# power_supply.net
KiCad netlist of a schematic drawn in Altium Designer
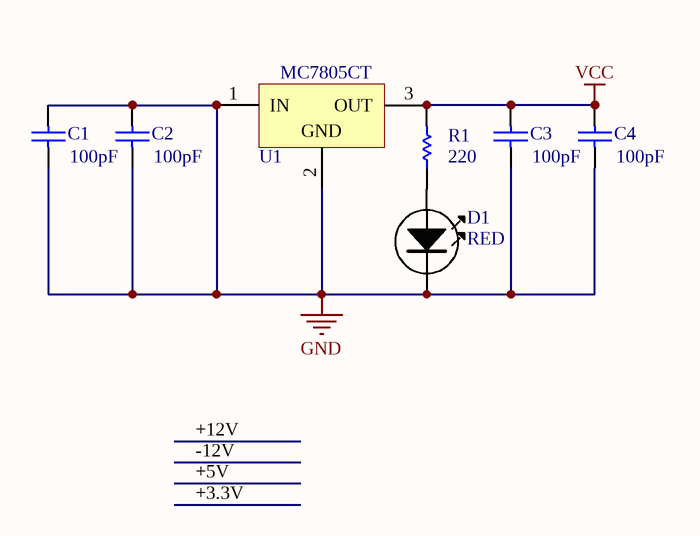
[diagram p0: power_supply.SchDoc]

(export (version "E")
  (design (tool "Eeschema 10.0.6"))
  (components
    (comp (ref "C1")
      (value "100pF")
      (footprint "RAD-0.3")
      (description "Capacitor")
      (fields (field (name "Comment") "Cap") (field (name "PUBLISHER") "Altium Limited"))
      (libsource (lib "Miscellaneous Devices") (part "Cap"))
    )
    (comp (ref "C2")
      (value "100pF")
      (footprint "RAD-0.3")
      (description "Capacitor")
      (fields (field (name "Comment") "Cap") (field (name "PUBLISHER") "Altium Limited"))
      (libsource (lib "Miscellaneous Devices") (part "Cap"))
    )
    (comp (ref "C3")
      (value "100pF")
      (footprint "RAD-0.3")
      (description "Capacitor")
      (fields (field (name "Comment") "Cap") (field (name "PUBLISHER") "Altium Limited"))
      (libsource (lib "Miscellaneous Devices") (part "Cap"))
    )
    (comp (ref "C4")
      (value "100pF")
      (footprint "RAD-0.3")
      (description "Capacitor")
      (fields (field (name "Comment") "Cap") (field (name "PUBLISHER") "Altium Limited"))
      (libsource (lib "Miscellaneous Devices") (part "Cap"))
    )
    (comp (ref "D1")
      (value "RED")
      (footprint "LED-5MM-RED")
      (description "LED-RED-5MM")
      (libsource (lib "vh_altium_library") (part "LED-RED-5MM"))
    )
    (comp (ref "R1")
      (value "220")
      (footprint "AXIAL-0.3")
      (description "Resistor")
      (fields (field (name "PUBLISHER") "Altium Limited"))
      (libsource (lib "Miscellaneous Devices") (part "Res1"))
    )
    (comp (ref "U1")
      (value "MC7805CT")
      (footprint "221A-06")
      (description "Three-Terminal Positive Voltage Regulator")
      (fields (field (name "PUBLISHER") "Altium Limited"))
      (libsource (lib "ON Semi Power Mgt Voltage Regulator") (part "MC7805CT"))
    )
  )
  (nets
    (net (code "5") (name "GND") (class "Default")
      (node (ref "C1") (pin "1") (pinfunction "1_1") (pintype "passive"))
      (node (ref "C1") (pin "2") (pinfunction "2_2") (pintype "passive"))
      (node (ref "C2") (pin "1") (pinfunction "1_1") (pintype "passive"))
      (node (ref "C2") (pin "2") (pinfunction "2_2") (pintype "passive"))
      (node (ref "C3") (pin "1") (pinfunction "1_1") (pintype "passive"))
      (node (ref "C4") (pin "1") (pinfunction "1_1") (pintype "passive"))
      (node (ref "D1") (pin "K") (pintype "passive"))
      (node (ref "U1") (pin "1") (pinfunction "IN_1") (pintype "power_in"))
      (node (ref "U1") (pin "2") (pinfunction "GND_2") (pintype "power_in"))
    )
    (net (code "6") (name "Net-(D1-PadA)") (class "Default")
      (node (ref "D1") (pin "A") (pintype "passive"))
      (node (ref "R1") (pin "1") (pinfunction "1_1") (pintype "passive"))
    )
    (net (code "7") (name "VCC") (class "Default")
      (node (ref "C3") (pin "2") (pinfunction "2_2") (pintype "passive"))
      (node (ref "C4") (pin "2") (pinfunction "2_2") (pintype "passive"))
      (node (ref "R1") (pin "2") (pinfunction "2_2") (pintype "passive"))
      (node (ref "U1") (pin "3") (pinfunction "OUT_3") (pintype "power_in"))
    )
  )
)
